# RF_Breakout_Boards.net
KiCad netlist of a schematic drawn in EAGLE
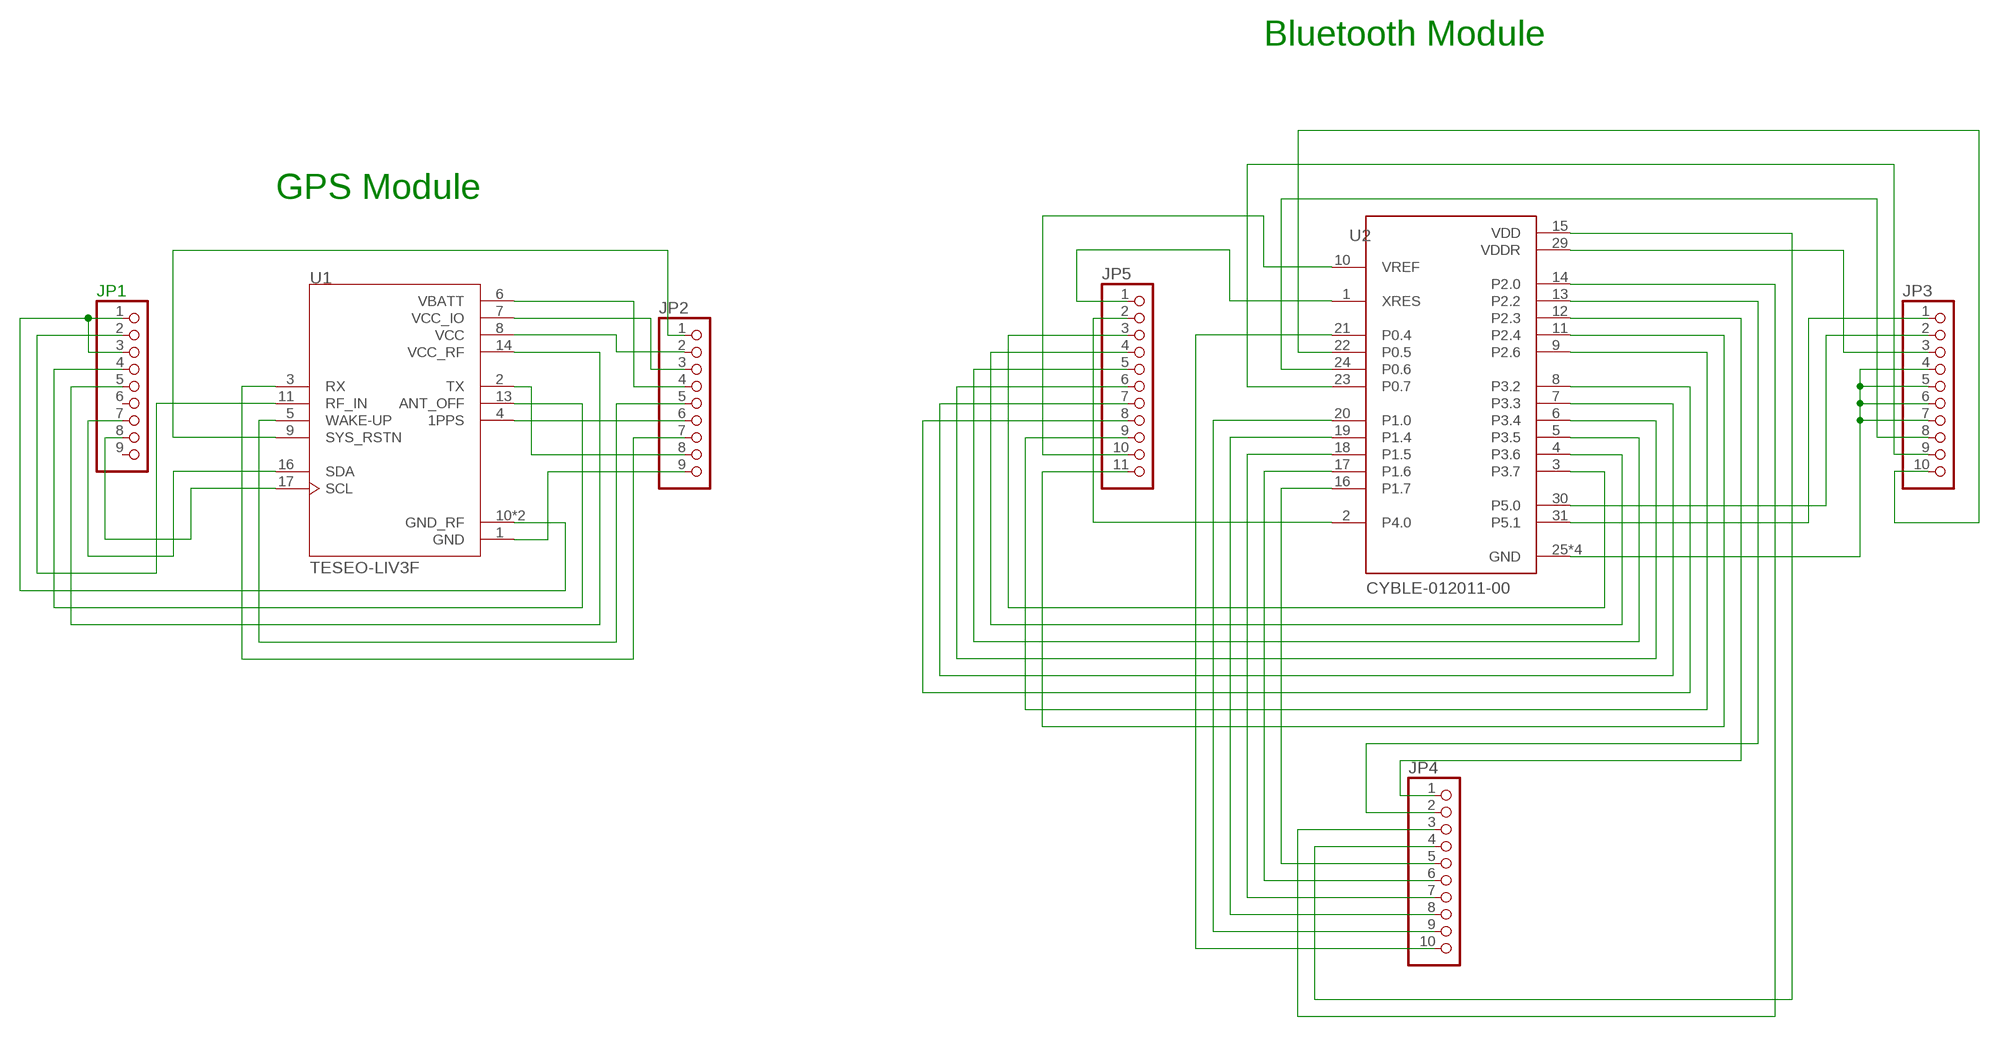
[diagram p0: schematic, sheet 1]

(export (version "E")
  (design (tool "Eeschema 10.0.6"))
  (components
    (comp (ref "JP1")
      (value "PINHD-1X9")
      (footprint "eagle-import:1X09")
      (libsource (lib "eagle-import") (part "PINHD-1X9"))
    )
    (comp (ref "JP2")
      (value "PINHD-1X9")
      (footprint "eagle-import:1X09")
      (libsource (lib "eagle-import") (part "PINHD-1X9"))
    )
    (comp (ref "JP3")
      (value "PINHD-1X10")
      (footprint "eagle-import:1X10")
      (libsource (lib "eagle-import") (part "PINHD-1X10"))
    )
    (comp (ref "JP4")
      (value "PINHD-1X10")
      (footprint "eagle-import:1X10")
      (libsource (lib "eagle-import") (part "PINHD-1X10"))
    )
    (comp (ref "JP5")
      (value "PINHD-1X11")
      (footprint "eagle-import:1X11")
      (libsource (lib "eagle-import") (part "PINHD-1X11"))
    )
    (comp (ref "U1")
      (value "TESEO-LIV3F")
      (footprint "eagle-import:TESEO-LIV3F")
      (fields (field (name "MF") "STMicroelectronics"))
      (libsource (lib "eagle-import") (part "TESEO-LIV3F"))
    )
    (comp (ref "U2")
      (value "CYBLE-012011-00")
      (footprint "eagle-import:XCVR_CYBLE-012011-00")
      (fields (field (name "MF") "Cypress Semiconductor"))
      (libsource (lib "eagle-import") (part "CYBLE-012011-00"))
    )
  )
  (nets
    (net (code "1") (name "Net-(JP1-Pad1)") (class "Default")
      (node (ref "JP1") (pin "1") (pinfunction "1_1") (pintype "passive"))
      (node (ref "JP1") (pin "3") (pinfunction "3_3") (pintype "passive"))
      (node (ref "U1") (pin "10") (pinfunction "GND_RF_10") (pintype "power_in"))
      (node (ref "U1") (pin "12") (pinfunction "GND_RF_12") (pintype "power_in"))
    )
    (net (code "2") (name "Net-(JP3-Pad4)") (class "Default")
      (node (ref "JP3") (pin "4") (pinfunction "4_4") (pintype "passive"))
      (node (ref "JP3") (pin "5") (pinfunction "5_5") (pintype "passive"))
      (node (ref "JP3") (pin "6") (pinfunction "6_6") (pintype "passive"))
      (node (ref "JP3") (pin "7") (pinfunction "7_7") (pintype "passive"))
      (node (ref "U2") (pin "25") (pinfunction "GND_25") (pintype "power_in"))
      (node (ref "U2") (pin "26") (pinfunction "GND_26") (pintype "power_in"))
      (node (ref "U2") (pin "27") (pinfunction "GND_27") (pintype "power_in"))
      (node (ref "U2") (pin "28") (pinfunction "GND_28") (pintype "power_in"))
    )
    (net (code "3") (name "Net-(U1-1PPS)") (class "Default")
      (node (ref "JP2") (pin "6") (pinfunction "6_6") (pintype "passive"))
      (node (ref "U1") (pin "4") (pinfunction "1PPS_4") (pintype "output"))
    )
    (net (code "4") (name "Net-(U1-ANT_OFF)") (class "Default")
      (node (ref "JP1") (pin "4") (pinfunction "4_4") (pintype "passive"))
      (node (ref "U1") (pin "13") (pinfunction "ANT_OFF_13") (pintype "output"))
    )
    (net (code "5") (name "Net-(U1-GND)") (class "Default")
      (node (ref "JP2") (pin "9") (pinfunction "9_9") (pintype "passive"))
      (node (ref "U1") (pin "1") (pinfunction "GND_1") (pintype "power_in"))
    )
    (net (code "6") (name "Net-(U1-RF_IN)") (class "Default")
      (node (ref "JP1") (pin "2") (pinfunction "2_2") (pintype "passive"))
      (node (ref "U1") (pin "11") (pinfunction "RF_IN_11") (pintype "input"))
    )
    (net (code "7") (name "Net-(U1-RX)") (class "Default")
      (node (ref "JP2") (pin "7") (pinfunction "7_7") (pintype "passive"))
      (node (ref "U1") (pin "3") (pinfunction "RX_3") (pintype "input"))
    )
    (net (code "8") (name "Net-(U1-SCL)") (class "Default")
      (node (ref "JP1") (pin "8") (pinfunction "8_8") (pintype "passive"))
      (node (ref "U1") (pin "17") (pinfunction "SCL_17") (pintype "bidirectional"))
    )
    (net (code "9") (name "Net-(U1-SDA)") (class "Default")
      (node (ref "JP1") (pin "7") (pinfunction "7_7") (pintype "passive"))
      (node (ref "U1") (pin "16") (pinfunction "SDA_16") (pintype "bidirectional"))
    )
    (net (code "10") (name "Net-(U1-SYS_RSTN)") (class "Default")
      (node (ref "JP2") (pin "1") (pinfunction "1_1") (pintype "passive"))
      (node (ref "U1") (pin "9") (pinfunction "SYS_RSTN_9") (pintype "input"))
    )
    (net (code "11") (name "Net-(U1-TX)") (class "Default")
      (node (ref "JP2") (pin "8") (pinfunction "8_8") (pintype "passive"))
      (node (ref "U1") (pin "2") (pinfunction "TX_2") (pintype "output"))
    )
    (net (code "12") (name "Net-(U1-VBATT)") (class "Default")
      (node (ref "JP2") (pin "4") (pinfunction "4_4") (pintype "passive"))
      (node (ref "U1") (pin "6") (pinfunction "VBATT_6") (pintype "power_in"))
    )
    (net (code "13") (name "Net-(U1-VCC)") (class "Default")
      (node (ref "JP2") (pin "2") (pinfunction "2_2") (pintype "passive"))
      (node (ref "U1") (pin "8") (pinfunction "VCC_8") (pintype "power_in"))
    )
    (net (code "14") (name "Net-(U1-VCC_IO)") (class "Default")
      (node (ref "JP2") (pin "3") (pinfunction "3_3") (pintype "passive"))
      (node (ref "U1") (pin "7") (pinfunction "VCC_IO_7") (pintype "power_in"))
    )
    (net (code "15") (name "Net-(U1-VCC_RF)") (class "Default")
      (node (ref "JP1") (pin "5") (pinfunction "5_5") (pintype "passive"))
      (node (ref "U1") (pin "14") (pinfunction "VCC_RF_14") (pintype "power_in"))
    )
    (net (code "16") (name "Net-(U1-WAKE-UP)") (class "Default")
      (node (ref "JP2") (pin "5") (pinfunction "5_5") (pintype "passive"))
      (node (ref "U1") (pin "5") (pinfunction "WAKE-UP_5") (pintype "input"))
    )
    (net (code "17") (name "Net-(U2-P0.4)") (class "Default")
      (node (ref "JP4") (pin "10") (pinfunction "10_10") (pintype "passive"))
      (node (ref "U2") (pin "21") (pinfunction "P0.4_21") (pintype "bidirectional"))
    )
    (net (code "18") (name "Net-(U2-P0.5)") (class "Default")
      (node (ref "JP3") (pin "10") (pinfunction "10_10") (pintype "passive"))
      (node (ref "U2") (pin "22") (pinfunction "P0.5_22") (pintype "bidirectional"))
    )
    (net (code "19") (name "Net-(U2-P0.6)") (class "Default")
      (node (ref "JP3") (pin "8") (pinfunction "8_8") (pintype "passive"))
      (node (ref "U2") (pin "24") (pinfunction "P0.6_24") (pintype "bidirectional"))
    )
    (net (code "20") (name "Net-(U2-P0.7)") (class "Default")
      (node (ref "JP3") (pin "9") (pinfunction "9_9") (pintype "passive"))
      (node (ref "U2") (pin "23") (pinfunction "P0.7_23") (pintype "bidirectional"))
    )
    (net (code "21") (name "Net-(U2-P1.0)") (class "Default")
      (node (ref "JP4") (pin "9") (pinfunction "9_9") (pintype "passive"))
      (node (ref "U2") (pin "20") (pinfunction "P1.0_20") (pintype "bidirectional"))
    )
    (net (code "22") (name "Net-(U2-P1.4)") (class "Default")
      (node (ref "JP4") (pin "8") (pinfunction "8_8") (pintype "passive"))
      (node (ref "U2") (pin "19") (pinfunction "P1.4_19") (pintype "bidirectional"))
    )
    (net (code "23") (name "Net-(U2-P1.5)") (class "Default")
      (node (ref "JP4") (pin "7") (pinfunction "7_7") (pintype "passive"))
      (node (ref "U2") (pin "18") (pinfunction "P1.5_18") (pintype "bidirectional"))
    )
    (net (code "24") (name "Net-(U2-P1.6)") (class "Default")
      (node (ref "JP4") (pin "6") (pinfunction "6_6") (pintype "passive"))
      (node (ref "U2") (pin "17") (pinfunction "P1.6_17") (pintype "bidirectional"))
    )
    (net (code "25") (name "Net-(U2-P1.7)") (class "Default")
      (node (ref "JP4") (pin "5") (pinfunction "5_5") (pintype "passive"))
      (node (ref "U2") (pin "16") (pinfunction "P1.7_16") (pintype "bidirectional"))
    )
    (net (code "26") (name "Net-(U2-P2.0)") (class "Default")
      (node (ref "JP4") (pin "3") (pinfunction "3_3") (pintype "passive"))
      (node (ref "U2") (pin "14") (pinfunction "P2.0_14") (pintype "bidirectional"))
    )
    (net (code "27") (name "Net-(U2-P2.2)") (class "Default")
      (node (ref "JP4") (pin "2") (pinfunction "2_2") (pintype "passive"))
      (node (ref "U2") (pin "13") (pinfunction "P2.2_13") (pintype "bidirectional"))
    )
    (net (code "28") (name "Net-(U2-P2.3)") (class "Default")
      (node (ref "JP4") (pin "1") (pinfunction "1_1") (pintype "passive"))
      (node (ref "U2") (pin "12") (pinfunction "P2.3_12") (pintype "bidirectional"))
    )
    (net (code "29") (name "Net-(U2-P2.4)") (class "Default")
      (node (ref "JP5") (pin "11") (pinfunction "11_11") (pintype "passive"))
      (node (ref "U2") (pin "11") (pinfunction "P2.4_11") (pintype "bidirectional"))
    )
    (net (code "30") (name "Net-(U2-P2.6)") (class "Default")
      (node (ref "JP5") (pin "9") (pinfunction "9_9") (pintype "passive"))
      (node (ref "U2") (pin "9") (pinfunction "P2.6_9") (pintype "bidirectional"))
    )
    (net (code "31") (name "Net-(U2-P3.2)") (class "Default")
      (node (ref "JP5") (pin "8") (pinfunction "8_8") (pintype "passive"))
      (node (ref "U2") (pin "8") (pinfunction "P3.2_8") (pintype "bidirectional"))
    )
    (net (code "32") (name "Net-(U2-P3.3)") (class "Default")
      (node (ref "JP5") (pin "7") (pinfunction "7_7") (pintype "passive"))
      (node (ref "U2") (pin "7") (pinfunction "P3.3_7") (pintype "bidirectional"))
    )
    (net (code "33") (name "Net-(U2-P3.4)") (class "Default")
      (node (ref "JP5") (pin "6") (pinfunction "6_6") (pintype "passive"))
      (node (ref "U2") (pin "6") (pinfunction "P3.4_6") (pintype "bidirectional"))
    )
    (net (code "34") (name "Net-(U2-P3.5)") (class "Default")
      (node (ref "JP5") (pin "5") (pinfunction "5_5") (pintype "passive"))
      (node (ref "U2") (pin "5") (pinfunction "P3.5_5") (pintype "bidirectional"))
    )
    (net (code "35") (name "Net-(U2-P3.6)") (class "Default")
      (node (ref "JP5") (pin "4") (pinfunction "4_4") (pintype "passive"))
      (node (ref "U2") (pin "4") (pinfunction "P3.6_4") (pintype "bidirectional"))
    )
    (net (code "36") (name "Net-(U2-P3.7)") (class "Default")
      (node (ref "JP5") (pin "3") (pinfunction "3_3") (pintype "passive"))
      (node (ref "U2") (pin "3") (pinfunction "P3.7_3") (pintype "bidirectional"))
    )
    (net (code "37") (name "Net-(U2-P4.0)") (class "Default")
      (node (ref "JP5") (pin "2") (pinfunction "2_2") (pintype "passive"))
      (node (ref "U2") (pin "2") (pinfunction "P4.0_2") (pintype "bidirectional"))
    )
    (net (code "38") (name "Net-(U2-P5.0)") (class "Default")
      (node (ref "JP3") (pin "2") (pinfunction "2_2") (pintype "passive"))
      (node (ref "U2") (pin "30") (pinfunction "P5.0_30") (pintype "bidirectional"))
    )
    (net (code "39") (name "Net-(U2-P5.1)") (class "Default")
      (node (ref "JP3") (pin "1") (pinfunction "1_1") (pintype "passive"))
      (node (ref "U2") (pin "31") (pinfunction "P5.1_31") (pintype "bidirectional"))
    )
    (net (code "40") (name "Net-(U2-VDD)") (class "Default")
      (node (ref "JP4") (pin "4") (pinfunction "4_4") (pintype "passive"))
      (node (ref "U2") (pin "15") (pinfunction "VDD_15") (pintype "power_in"))
    )
    (net (code "41") (name "Net-(U2-VDDR)") (class "Default")
      (node (ref "JP3") (pin "3") (pinfunction "3_3") (pintype "passive"))
      (node (ref "U2") (pin "29") (pinfunction "VDDR_29") (pintype "power_in"))
    )
    (net (code "42") (name "Net-(U2-VREF)") (class "Default")
      (node (ref "JP5") (pin "10") (pinfunction "10_10") (pintype "passive"))
      (node (ref "U2") (pin "10") (pinfunction "VREF_10") (pintype "input"))
    )
    (net (code "43") (name "Net-(U2-XRES)") (class "Default")
      (node (ref "JP5") (pin "1") (pinfunction "1_1") (pintype "passive"))
      (node (ref "U2") (pin "1") (pinfunction "XRES_1") (pintype "input"))
    )
    (net (code "44") (name "unconnected-(JP1-Pad6)") (class "Default")
      (node (ref "JP1") (pin "6") (pinfunction "6_6") (pintype "passive"))
    )
    (net (code "45") (name "unconnected-(JP1-Pad9)") (class "Default")
      (node (ref "JP1") (pin "9") (pinfunction "9_9") (pintype "passive"))
    )
  )
)
